# 2_1_bus_breakout.net
KiCad netlist of a schematic drawn in Altium Designer
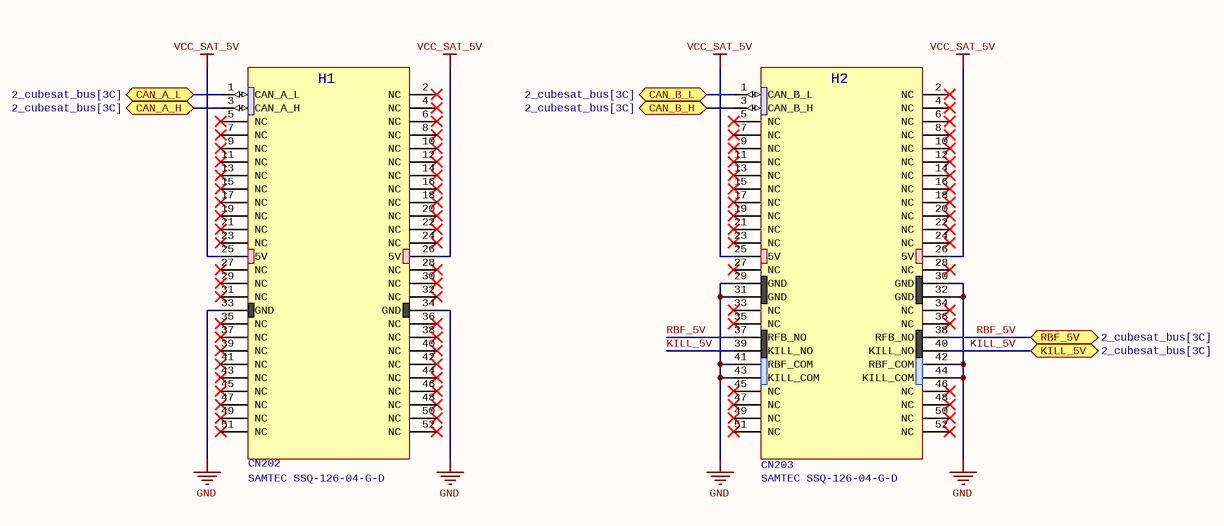
[diagram p0: 2_1_bus_breakout.SchDoc]

(export (version "E")
  (design (tool "Eeschema 10.0.6"))
  (components
    (comp (ref "CN202")
      (value "SAMTEC SSQ-126-04-G-D")
      (footprint "SAMTEC SSQ NO 3D")
      (description "LoRa Payload only pins SAMTEC SSQ-126-04-G-D")
      (libsource (lib "cubesat_bus") (part "CubeSat Header H1 LoRa PL"))
    )
    (comp (ref "CN203")
      (value "SAMTEC SSQ-126-04-G-D")
      (footprint "SAMTEC SSQ NO 3D")
      (description "LoRa Payload only pins")
      (libsource (lib "cubesat_bus") (part "CubeSat Header H2 LoRa PL"))
    )
  )
  (nets
    (net (code "1") (name "/CAN_A_H") (class "Default")
      (node (ref "CN202") (pin "3") (pinfunction "CAN_A_H_3") (pintype "bidirectional"))
    )
    (net (code "2") (name "/CAN_A_L") (class "Default")
      (node (ref "CN202") (pin "1") (pinfunction "CAN_A_L_1") (pintype "bidirectional"))
    )
    (net (code "3") (name "/CAN_B_H") (class "Default")
      (node (ref "CN203") (pin "3") (pinfunction "CAN_B_H_3") (pintype "bidirectional"))
    )
    (net (code "4") (name "/CAN_B_L") (class "Default")
      (node (ref "CN203") (pin "1") (pinfunction "CAN_B_L_1") (pintype "bidirectional"))
    )
    (net (code "5") (name "/KILL_5V") (class "Default")
      (node (ref "CN203") (pin "39") (pinfunction "KILL_NO_39") (pintype "passive"))
      (node (ref "CN203") (pin "40") (pinfunction "KILL_NO_40") (pintype "passive"))
    )
    (net (code "6") (name "/RBF_5V") (class "Default")
      (node (ref "CN203") (pin "37") (pinfunction "RFB_NO_37") (pintype "passive"))
      (node (ref "CN203") (pin "38") (pinfunction "RFB_NO_38") (pintype "passive"))
    )
    (net (code "7") (name "GND") (class "Default")
      (node (ref "CN202") (pin "33") (pinfunction "GND_33") (pintype "power_in"))
      (node (ref "CN202") (pin "34") (pinfunction "GND_34") (pintype "power_in"))
      (node (ref "CN203") (pin "29") (pinfunction "GND_29") (pintype "power_in"))
      (node (ref "CN203") (pin "30") (pinfunction "GND_30") (pintype "power_in"))
      (node (ref "CN203") (pin "31") (pinfunction "GND_31") (pintype "power_in"))
      (node (ref "CN203") (pin "32") (pinfunction "GND_32") (pintype "power_in"))
      (node (ref "CN203") (pin "41") (pinfunction "RBF_COM_41") (pintype "passive"))
      (node (ref "CN203") (pin "42") (pinfunction "RBF_COM_42") (pintype "passive"))
      (node (ref "CN203") (pin "43") (pinfunction "KILL_COM_43") (pintype "passive"))
      (node (ref "CN203") (pin "44") (pinfunction "KILL_COM_44") (pintype "passive"))
    )
    (net (code "8") (name "VCC_SAT_5V") (class "Default")
      (node (ref "CN202") (pin "25") (pinfunction "5V_25") (pintype "power_in"))
      (node (ref "CN202") (pin "26") (pinfunction "5V_26") (pintype "power_in"))
      (node (ref "CN203") (pin "25") (pinfunction "5V_25") (pintype "power_in"))
      (node (ref "CN203") (pin "26") (pinfunction "5V_26") (pintype "power_in"))
    )
    (net (code "9") (name "unconnected-(CN202-NC-Pad2)") (class "Default")
      (node (ref "CN202") (pin "2") (pinfunction "NC_2") (pintype "passive+no_connect"))
    )
    (net (code "10") (name "unconnected-(CN202-NC-Pad4)") (class "Default")
      (node (ref "CN202") (pin "4") (pinfunction "NC_4") (pintype "passive+no_connect"))
    )
    (net (code "11") (name "unconnected-(CN202-NC-Pad5)") (class "Default")
      (node (ref "CN202") (pin "5") (pinfunction "NC_5") (pintype "passive+no_connect"))
    )
    (net (code "12") (name "unconnected-(CN202-NC-Pad6)") (class "Default")
      (node (ref "CN202") (pin "6") (pinfunction "NC_6") (pintype "passive+no_connect"))
    )
    (net (code "13") (name "unconnected-(CN202-NC-Pad7)") (class "Default")
      (node (ref "CN202") (pin "7") (pinfunction "NC_7") (pintype "passive+no_connect"))
    )
    (net (code "14") (name "unconnected-(CN202-NC-Pad8)") (class "Default")
      (node (ref "CN202") (pin "8") (pinfunction "NC_8") (pintype "passive+no_connect"))
    )
    (net (code "15") (name "unconnected-(CN202-NC-Pad9)") (class "Default")
      (node (ref "CN202") (pin "9") (pinfunction "NC_9") (pintype "passive+no_connect"))
    )
    (net (code "16") (name "unconnected-(CN202-NC-Pad10)") (class "Default")
      (node (ref "CN202") (pin "10") (pinfunction "NC_10") (pintype "passive+no_connect"))
    )
    (net (code "17") (name "unconnected-(CN202-NC-Pad11)") (class "Default")
      (node (ref "CN202") (pin "11") (pinfunction "NC_11") (pintype "passive+no_connect"))
    )
    (net (code "18") (name "unconnected-(CN202-NC-Pad12)") (class "Default")
      (node (ref "CN202") (pin "12") (pinfunction "NC_12") (pintype "passive+no_connect"))
    )
    (net (code "19") (name "unconnected-(CN202-NC-Pad13)") (class "Default")
      (node (ref "CN202") (pin "13") (pinfunction "NC_13") (pintype "passive+no_connect"))
    )
    (net (code "20") (name "unconnected-(CN202-NC-Pad14)") (class "Default")
      (node (ref "CN202") (pin "14") (pinfunction "NC_14") (pintype "passive+no_connect"))
    )
    (net (code "21") (name "unconnected-(CN202-NC-Pad15)") (class "Default")
      (node (ref "CN202") (pin "15") (pinfunction "NC_15") (pintype "passive+no_connect"))
    )
    (net (code "22") (name "unconnected-(CN202-NC-Pad16)") (class "Default")
      (node (ref "CN202") (pin "16") (pinfunction "NC_16") (pintype "passive+no_connect"))
    )
    (net (code "23") (name "unconnected-(CN202-NC-Pad17)") (class "Default")
      (node (ref "CN202") (pin "17") (pinfunction "NC_17") (pintype "passive+no_connect"))
    )
    (net (code "24") (name "unconnected-(CN202-NC-Pad18)") (class "Default")
      (node (ref "CN202") (pin "18") (pinfunction "NC_18") (pintype "passive+no_connect"))
    )
    (net (code "25") (name "unconnected-(CN202-NC-Pad19)") (class "Default")
      (node (ref "CN202") (pin "19") (pinfunction "NC_19") (pintype "passive+no_connect"))
    )
    (net (code "26") (name "unconnected-(CN202-NC-Pad20)") (class "Default")
      (node (ref "CN202") (pin "20") (pinfunction "NC_20") (pintype "passive+no_connect"))
    )
    (net (code "27") (name "unconnected-(CN202-NC-Pad21)") (class "Default")
      (node (ref "CN202") (pin "21") (pinfunction "NC_21") (pintype "passive+no_connect"))
    )
    (net (code "28") (name "unconnected-(CN202-NC-Pad22)") (class "Default")
      (node (ref "CN202") (pin "22") (pinfunction "NC_22") (pintype "passive+no_connect"))
    )
    (net (code "29") (name "unconnected-(CN202-NC-Pad23)") (class "Default")
      (node (ref "CN202") (pin "23") (pinfunction "NC_23") (pintype "passive+no_connect"))
    )
    (net (code "30") (name "unconnected-(CN202-NC-Pad24)") (class "Default")
      (node (ref "CN202") (pin "24") (pinfunction "NC_24") (pintype "passive+no_connect"))
    )
    (net (code "31") (name "unconnected-(CN202-NC-Pad27)") (class "Default")
      (node (ref "CN202") (pin "27") (pinfunction "NC_27") (pintype "passive+no_connect"))
    )
    (net (code "32") (name "unconnected-(CN202-NC-Pad28)") (class "Default")
      (node (ref "CN202") (pin "28") (pinfunction "NC_28") (pintype "passive+no_connect"))
    )
    (net (code "33") (name "unconnected-(CN202-NC-Pad29)") (class "Default")
      (node (ref "CN202") (pin "29") (pinfunction "NC_29") (pintype "passive+no_connect"))
    )
    (net (code "34") (name "unconnected-(CN202-NC-Pad30)") (class "Default")
      (node (ref "CN202") (pin "30") (pinfunction "NC_30") (pintype "passive+no_connect"))
    )
    (net (code "35") (name "unconnected-(CN202-NC-Pad31)") (class "Default")
      (node (ref "CN202") (pin "31") (pinfunction "NC_31") (pintype "passive+no_connect"))
    )
    (net (code "36") (name "unconnected-(CN202-NC-Pad32)") (class "Default")
      (node (ref "CN202") (pin "32") (pinfunction "NC_32") (pintype "passive+no_connect"))
    )
    (net (code "37") (name "unconnected-(CN202-NC-Pad35)") (class "Default")
      (node (ref "CN202") (pin "35") (pinfunction "NC_35") (pintype "passive+no_connect"))
    )
    (net (code "38") (name "unconnected-(CN202-NC-Pad36)") (class "Default")
      (node (ref "CN202") (pin "36") (pinfunction "NC_36") (pintype "passive+no_connect"))
    )
    (net (code "39") (name "unconnected-(CN202-NC-Pad37)") (class "Default")
      (node (ref "CN202") (pin "37") (pinfunction "NC_37") (pintype "passive+no_connect"))
    )
    (net (code "40") (name "unconnected-(CN202-NC-Pad38)") (class "Default")
      (node (ref "CN202") (pin "38") (pinfunction "NC_38") (pintype "passive+no_connect"))
    )
    (net (code "41") (name "unconnected-(CN202-NC-Pad39)") (class "Default")
      (node (ref "CN202") (pin "39") (pinfunction "NC_39") (pintype "passive+no_connect"))
    )
    (net (code "42") (name "unconnected-(CN202-NC-Pad40)") (class "Default")
      (node (ref "CN202") (pin "40") (pinfunction "NC_40") (pintype "passive+no_connect"))
    )
    (net (code "43") (name "unconnected-(CN202-NC-Pad41)") (class "Default")
      (node (ref "CN202") (pin "41") (pinfunction "NC_41") (pintype "passive+no_connect"))
    )
    (net (code "44") (name "unconnected-(CN202-NC-Pad42)") (class "Default")
      (node (ref "CN202") (pin "42") (pinfunction "NC_42") (pintype "passive+no_connect"))
    )
    (net (code "45") (name "unconnected-(CN202-NC-Pad43)") (class "Default")
      (node (ref "CN202") (pin "43") (pinfunction "NC_43") (pintype "passive+no_connect"))
    )
    (net (code "46") (name "unconnected-(CN202-NC-Pad44)") (class "Default")
      (node (ref "CN202") (pin "44") (pinfunction "NC_44") (pintype "passive+no_connect"))
    )
    (net (code "47") (name "unconnected-(CN202-NC-Pad45)") (class "Default")
      (node (ref "CN202") (pin "45") (pinfunction "NC_45") (pintype "passive+no_connect"))
    )
    (net (code "48") (name "unconnected-(CN202-NC-Pad46)") (class "Default")
      (node (ref "CN202") (pin "46") (pinfunction "NC_46") (pintype "passive+no_connect"))
    )
    (net (code "49") (name "unconnected-(CN202-NC-Pad47)") (class "Default")
      (node (ref "CN202") (pin "47") (pinfunction "NC_47") (pintype "passive+no_connect"))
    )
    (net (code "50") (name "unconnected-(CN202-NC-Pad48)") (class "Default")
      (node (ref "CN202") (pin "48") (pinfunction "NC_48") (pintype "passive+no_connect"))
    )
    (net (code "51") (name "unconnected-(CN202-NC-Pad49)") (class "Default")
      (node (ref "CN202") (pin "49") (pinfunction "NC_49") (pintype "passive+no_connect"))
    )
    (net (code "52") (name "unconnected-(CN202-NC-Pad50)") (class "Default")
      (node (ref "CN202") (pin "50") (pinfunction "NC_50") (pintype "passive+no_connect"))
    )
    (net (code "53") (name "unconnected-(CN202-NC-Pad51)") (class "Default")
      (node (ref "CN202") (pin "51") (pinfunction "NC_51") (pintype "passive+no_connect"))
    )
    (net (code "54") (name "unconnected-(CN202-NC-Pad52)") (class "Default")
      (node (ref "CN202") (pin "52") (pinfunction "NC_52") (pintype "passive+no_connect"))
    )
    (net (code "55") (name "unconnected-(CN203-NC-Pad2)") (class "Default")
      (node (ref "CN203") (pin "2") (pinfunction "NC_2") (pintype "passive+no_connect"))
    )
    (net (code "56") (name "unconnected-(CN203-NC-Pad4)") (class "Default")
      (node (ref "CN203") (pin "4") (pinfunction "NC_4") (pintype "passive+no_connect"))
    )
    (net (code "57") (name "unconnected-(CN203-NC-Pad5)") (class "Default")
      (node (ref "CN203") (pin "5") (pinfunction "NC_5") (pintype "passive+no_connect"))
    )
    (net (code "58") (name "unconnected-(CN203-NC-Pad6)") (class "Default")
      (node (ref "CN203") (pin "6") (pinfunction "NC_6") (pintype "passive+no_connect"))
    )
    (net (code "59") (name "unconnected-(CN203-NC-Pad7)") (class "Default")
      (node (ref "CN203") (pin "7") (pinfunction "NC_7") (pintype "passive+no_connect"))
    )
    (net (code "60") (name "unconnected-(CN203-NC-Pad8)") (class "Default")
      (node (ref "CN203") (pin "8") (pinfunction "NC_8") (pintype "passive+no_connect"))
    )
    (net (code "61") (name "unconnected-(CN203-NC-Pad9)") (class "Default")
      (node (ref "CN203") (pin "9") (pinfunction "NC_9") (pintype "passive+no_connect"))
    )
    (net (code "62") (name "unconnected-(CN203-NC-Pad10)") (class "Default")
      (node (ref "CN203") (pin "10") (pinfunction "NC_10") (pintype "passive+no_connect"))
    )
    (net (code "63") (name "unconnected-(CN203-NC-Pad11)") (class "Default")
      (node (ref "CN203") (pin "11") (pinfunction "NC_11") (pintype "passive+no_connect"))
    )
    (net (code "64") (name "unconnected-(CN203-NC-Pad12)") (class "Default")
      (node (ref "CN203") (pin "12") (pinfunction "NC_12") (pintype "passive+no_connect"))
    )
    (net (code "65") (name "unconnected-(CN203-NC-Pad13)") (class "Default")
      (node (ref "CN203") (pin "13") (pinfunction "NC_13") (pintype "passive+no_connect"))
    )
    (net (code "66") (name "unconnected-(CN203-NC-Pad14)") (class "Default")
      (node (ref "CN203") (pin "14") (pinfunction "NC_14") (pintype "passive+no_connect"))
    )
    (net (code "67") (name "unconnected-(CN203-NC-Pad15)") (class "Default")
      (node (ref "CN203") (pin "15") (pinfunction "NC_15") (pintype "passive+no_connect"))
    )
    (net (code "68") (name "unconnected-(CN203-NC-Pad16)") (class "Default")
      (node (ref "CN203") (pin "16") (pinfunction "NC_16") (pintype "passive+no_connect"))
    )
    (net (code "69") (name "unconnected-(CN203-NC-Pad17)") (class "Default")
      (node (ref "CN203") (pin "17") (pinfunction "NC_17") (pintype "passive+no_connect"))
    )
    (net (code "70") (name "unconnected-(CN203-NC-Pad18)") (class "Default")
      (node (ref "CN203") (pin "18") (pinfunction "NC_18") (pintype "passive+no_connect"))
    )
    (net (code "71") (name "unconnected-(CN203-NC-Pad19)") (class "Default")
      (node (ref "CN203") (pin "19") (pinfunction "NC_19") (pintype "passive+no_connect"))
    )
    (net (code "72") (name "unconnected-(CN203-NC-Pad20)") (class "Default")
      (node (ref "CN203") (pin "20") (pinfunction "NC_20") (pintype "passive+no_connect"))
    )
    (net (code "73") (name "unconnected-(CN203-NC-Pad21)") (class "Default")
      (node (ref "CN203") (pin "21") (pinfunction "NC_21") (pintype "passive+no_connect"))
    )
    (net (code "74") (name "unconnected-(CN203-NC-Pad22)") (class "Default")
      (node (ref "CN203") (pin "22") (pinfunction "NC_22") (pintype "passive+no_connect"))
    )
    (net (code "75") (name "unconnected-(CN203-NC-Pad23)") (class "Default")
      (node (ref "CN203") (pin "23") (pinfunction "NC_23") (pintype "passive+no_connect"))
    )
    (net (code "76") (name "unconnected-(CN203-NC-Pad24)") (class "Default")
      (node (ref "CN203") (pin "24") (pinfunction "NC_24") (pintype "passive+no_connect"))
    )
    (net (code "77") (name "unconnected-(CN203-NC-Pad27)") (class "Default")
      (node (ref "CN203") (pin "27") (pinfunction "NC_27") (pintype "passive+no_connect"))
    )
    (net (code "78") (name "unconnected-(CN203-NC-Pad28)") (class "Default")
      (node (ref "CN203") (pin "28") (pinfunction "NC_28") (pintype "passive+no_connect"))
    )
    (net (code "79") (name "unconnected-(CN203-NC-Pad33)") (class "Default")
      (node (ref "CN203") (pin "33") (pinfunction "NC_33") (pintype "passive+no_connect"))
    )
    (net (code "80") (name "unconnected-(CN203-NC-Pad34)") (class "Default")
      (node (ref "CN203") (pin "34") (pinfunction "NC_34") (pintype "passive+no_connect"))
    )
    (net (code "81") (name "unconnected-(CN203-NC-Pad35)") (class "Default")
      (node (ref "CN203") (pin "35") (pinfunction "NC_35") (pintype "passive+no_connect"))
    )
    (net (code "82") (name "unconnected-(CN203-NC-Pad36)") (class "Default")
      (node (ref "CN203") (pin "36") (pinfunction "NC_36") (pintype "passive+no_connect"))
    )
    (net (code "83") (name "unconnected-(CN203-NC-Pad45)") (class "Default")
      (node (ref "CN203") (pin "45") (pinfunction "NC_45") (pintype "power_in+no_connect"))
    )
    (net (code "84") (name "unconnected-(CN203-NC-Pad46)") (class "Default")
      (node (ref "CN203") (pin "46") (pinfunction "NC_46") (pintype "power_in+no_connect"))
    )
    (net (code "85") (name "unconnected-(CN203-NC-Pad47)") (class "Default")
      (node (ref "CN203") (pin "47") (pinfunction "NC_47") (pintype "passive+no_connect"))
    )
    (net (code "86") (name "unconnected-(CN203-NC-Pad48)") (class "Default")
      (node (ref "CN203") (pin "48") (pinfunction "NC_48") (pintype "passive+no_connect"))
    )
    (net (code "87") (name "unconnected-(CN203-NC-Pad49)") (class "Default")
      (node (ref "CN203") (pin "49") (pinfunction "NC_49") (pintype "passive+no_connect"))
    )
    (net (code "88") (name "unconnected-(CN203-NC-Pad50)") (class "Default")
      (node (ref "CN203") (pin "50") (pinfunction "NC_50") (pintype "passive+no_connect"))
    )
    (net (code "89") (name "unconnected-(CN203-NC-Pad51)") (class "Default")
      (node (ref "CN203") (pin "51") (pinfunction "NC_51") (pintype "passive+no_connect"))
    )
    (net (code "90") (name "unconnected-(CN203-NC-Pad52)") (class "Default")
      (node (ref "CN203") (pin "52") (pinfunction "NC_52") (pintype "passive+no_connect"))
    )
  )
)
